# apc556fix.net
KiCad netlist of a schematic drawn in EAGLE
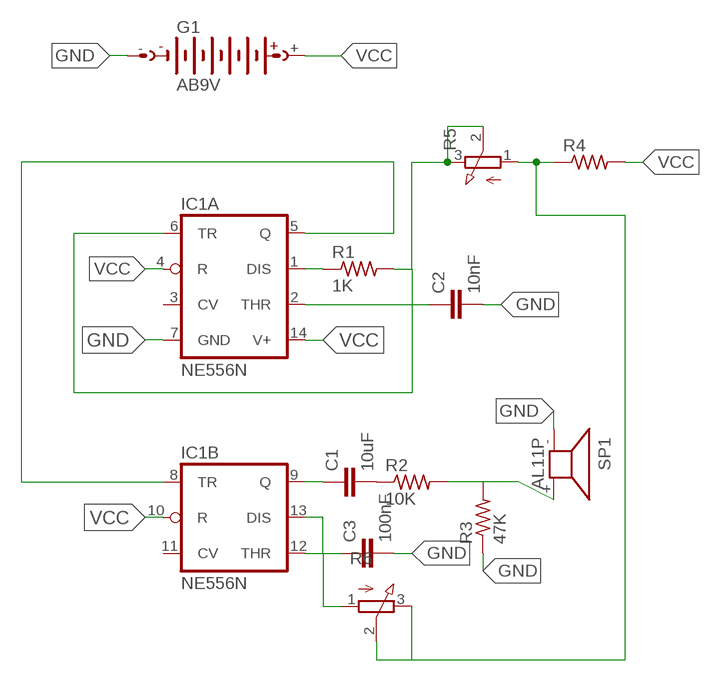
[diagram p0: schematic, sheet 1]

(export (version "E")
  (design (tool "Eeschema 10.0.6"))
  (components
    (comp (ref "C1")
      (value "10uF")
      (footprint "eagle-import:C025-030X050")
      (libsource (lib "eagle-import") (part "C-EU025-030X050"))
    )
    (comp (ref "C2")
      (value "10nF")
      (footprint "eagle-import:C025-030X050")
      (libsource (lib "eagle-import") (part "C-EU025-030X050"))
    )
    (comp (ref "C3")
      (value "100nF")
      (footprint "eagle-import:C025-030X050")
      (libsource (lib "eagle-import") (part "C-EU025-030X050"))
    )
    (comp (ref "G1")
      (value "AB9V")
      (footprint "eagle-import:AB9V")
      (libsource (lib "eagle-import") (part "AB9V"))
    )
    (comp (ref "IC1")
      (value "NE556N")
      (footprint "eagle-import:DIL14")
      (libsource (lib "eagle-import") (part "556NNE"))
    )
    (comp (ref "R1")
      (value "1K")
      (footprint "eagle-import:0204_5")
      (libsource (lib "eagle-import") (part "R-US_0204/5"))
    )
    (comp (ref "R2")
      (value "10K")
      (footprint "eagle-import:0204_7")
      (libsource (lib "eagle-import") (part "R-US_0204/7"))
    )
    (comp (ref "R3")
      (value "47K")
      (footprint "eagle-import:0204_7")
      (libsource (lib "eagle-import") (part "R-US_0204/7"))
    )
    (comp (ref "R4")
      (value "R-US_0204/7")
      (footprint "eagle-import:0204_7")
      (libsource (lib "eagle-import") (part "R-US_0204/7"))
    )
    (comp (ref "R5")
      (value "3RP/1610N")
      (footprint "eagle-import:3RP_1610N")
      (libsource (lib "eagle-import") (part "3RP/1610N"))
    )
    (comp (ref "R6")
      (value "3RP/1610N")
      (footprint "eagle-import:3RP_1610N")
      (libsource (lib "eagle-import") (part "3RP/1610N"))
    )
    (comp (ref "SP1")
      (value "AL11P")
      (footprint "eagle-import:AL11P")
      (libsource (lib "eagle-import") (part "AL11P"))
    )
  )
  (nets
    (net (code "1") (name "GND") (class "Default")
      (node (ref "C2") (pin "2") (pinfunction "2_2") (pintype "passive"))
      (node (ref "C3") (pin "2") (pinfunction "2_2") (pintype "passive"))
      (node (ref "G1") (pin "-") (pinfunction "-_-") (pintype "passive"))
      (node (ref "IC1") (pin "7") (pinfunction "GND_7") (pintype "power_in"))
      (node (ref "R3") (pin "1") (pinfunction "1_1") (pintype "passive"))
      (node (ref "SP1") (pin "-") (pinfunction "1_-") (pintype "passive"))
    )
    (net (code "2") (name "Net-(C1-Pad2)") (class "Default")
      (node (ref "C1") (pin "2") (pinfunction "2_2") (pintype "passive"))
      (node (ref "R2") (pin "1") (pinfunction "1_1") (pintype "passive"))
    )
    (net (code "3") (name "Net-(IC1A-DIS)") (class "Default")
      (node (ref "IC1") (pin "1") (pinfunction "DIS_1") (pintype "input"))
      (node (ref "R1") (pin "1") (pinfunction "1_1") (pintype "passive"))
    )
    (net (code "4") (name "Net-(IC1A-Q)") (class "Default")
      (node (ref "IC1") (pin "5") (pinfunction "Q_5") (pintype "output"))
      (node (ref "IC1") (pin "8") (pinfunction "TR_8") (pintype "input"))
    )
    (net (code "5") (name "Net-(IC1A-THR)") (class "Default")
      (node (ref "C2") (pin "1") (pinfunction "1_1") (pintype "passive"))
      (node (ref "IC1") (pin "2") (pinfunction "THR_2") (pintype "input"))
      (node (ref "IC1") (pin "6") (pinfunction "TR_6") (pintype "input"))
      (node (ref "R1") (pin "2") (pinfunction "2_2") (pintype "passive"))
      (node (ref "R5") (pin "2") (pinfunction "S_2") (pintype "passive"))
      (node (ref "R5") (pin "3") (pinfunction "E_3") (pintype "passive"))
    )
    (net (code "6") (name "Net-(IC1B-DIS)") (class "Default")
      (node (ref "C3") (pin "1") (pinfunction "1_1") (pintype "passive"))
      (node (ref "IC1") (pin "12") (pinfunction "THR_12") (pintype "input"))
      (node (ref "IC1") (pin "13") (pinfunction "DIS_13") (pintype "input"))
      (node (ref "R6") (pin "1") (pinfunction "A_1") (pintype "passive"))
    )
    (net (code "7") (name "Net-(IC1B-Q)") (class "Default")
      (node (ref "C1") (pin "1") (pinfunction "1_1") (pintype "passive"))
      (node (ref "IC1") (pin "9") (pinfunction "Q_9") (pintype "output"))
    )
    (net (code "8") (name "Net-(R5-A)") (class "Default")
      (node (ref "R4") (pin "1") (pinfunction "1_1") (pintype "passive"))
      (node (ref "R5") (pin "1") (pinfunction "A_1") (pintype "passive"))
      (node (ref "R6") (pin "2") (pinfunction "S_2") (pintype "passive"))
      (node (ref "R6") (pin "3") (pinfunction "E_3") (pintype "passive"))
    )
    (net (code "9") (name "Net-(SP1-2)") (class "Default")
      (node (ref "R2") (pin "2") (pinfunction "2_2") (pintype "passive"))
      (node (ref "R3") (pin "2") (pinfunction "2_2") (pintype "passive"))
      (node (ref "SP1") (pin "+") (pinfunction "2_+") (pintype "passive"))
    )
    (net (code "10") (name "VCC") (class "Default")
      (node (ref "G1") (pin "+") (pinfunction "+_+") (pintype "passive"))
      (node (ref "IC1") (pin "10") (pinfunction "R_10") (pintype "input"))
      (node (ref "IC1") (pin "14") (pinfunction "V+_14") (pintype "power_in"))
      (node (ref "IC1") (pin "4") (pinfunction "R_4") (pintype "input"))
      (node (ref "R4") (pin "2") (pinfunction "2_2") (pintype "passive"))
    )
    (net (code "11") (name "unconnected-(IC1A-CV-Pad3)") (class "Default")
      (node (ref "IC1") (pin "3") (pinfunction "CV_3") (pintype "input"))
    )
    (net (code "12") (name "unconnected-(IC1B-CV-Pad11)") (class "Default")
      (node (ref "IC1") (pin "11") (pinfunction "CV_11") (pintype "input"))
    )
  )
)
